# Grove_-_Tilt_Switch_v1_0.net
KiCad netlist of a schematic drawn in EAGLE
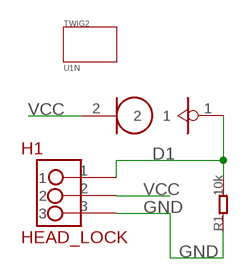
[diagram p0: schematic, sheet 1]

(export (version "E")
  (design (tool "Eeschema 10.0.6"))
  (components
    (comp (ref "H1")
      (value "HEAD_LOCK")
      (footprint "eagle-import:HEAD_LOCK")
      (libsource (lib "eagle-import") (part "HEAD_LOCK"))
    )
    (comp (ref "J1")
      (value "TILT")
      (footprint "eagle-import:TILT")
      (libsource (lib "eagle-import") (part "TILT"))
    )
    (comp (ref "R1")
      (value "10k")
      (footprint "eagle-import:0603")
      (libsource (lib "eagle-import") (part "005-R0603"))
    )
    (comp (ref "TWIG2")
      (value "U1N")
      (footprint "eagle-import:U1N")
      (libsource (lib "eagle-import") (part "U1N"))
    )
  )
  (nets
    (net (code "1") (name "/D1") (class "Default")
      (node (ref "H1") (pin "1") (pinfunction "1_1") (pintype "passive"))
      (node (ref "J1") (pin "1") (pinfunction "1_1") (pintype "bidirectional"))
      (node (ref "R1") (pin "2") (pinfunction "2_2") (pintype "passive"))
    )
    (net (code "2") (name "/GND") (class "Default")
      (node (ref "H1") (pin "3") (pinfunction "3_3") (pintype "passive"))
      (node (ref "R1") (pin "1") (pinfunction "1_1") (pintype "passive"))
    )
    (net (code "3") (name "/VCC") (class "Default")
      (node (ref "H1") (pin "2") (pinfunction "2_2") (pintype "passive"))
      (node (ref "J1") (pin "2") (pinfunction "2_2") (pintype "bidirectional"))
    )
  )
)
